# LoNet_808.net
KiCad netlist of a schematic drawn in EAGLE
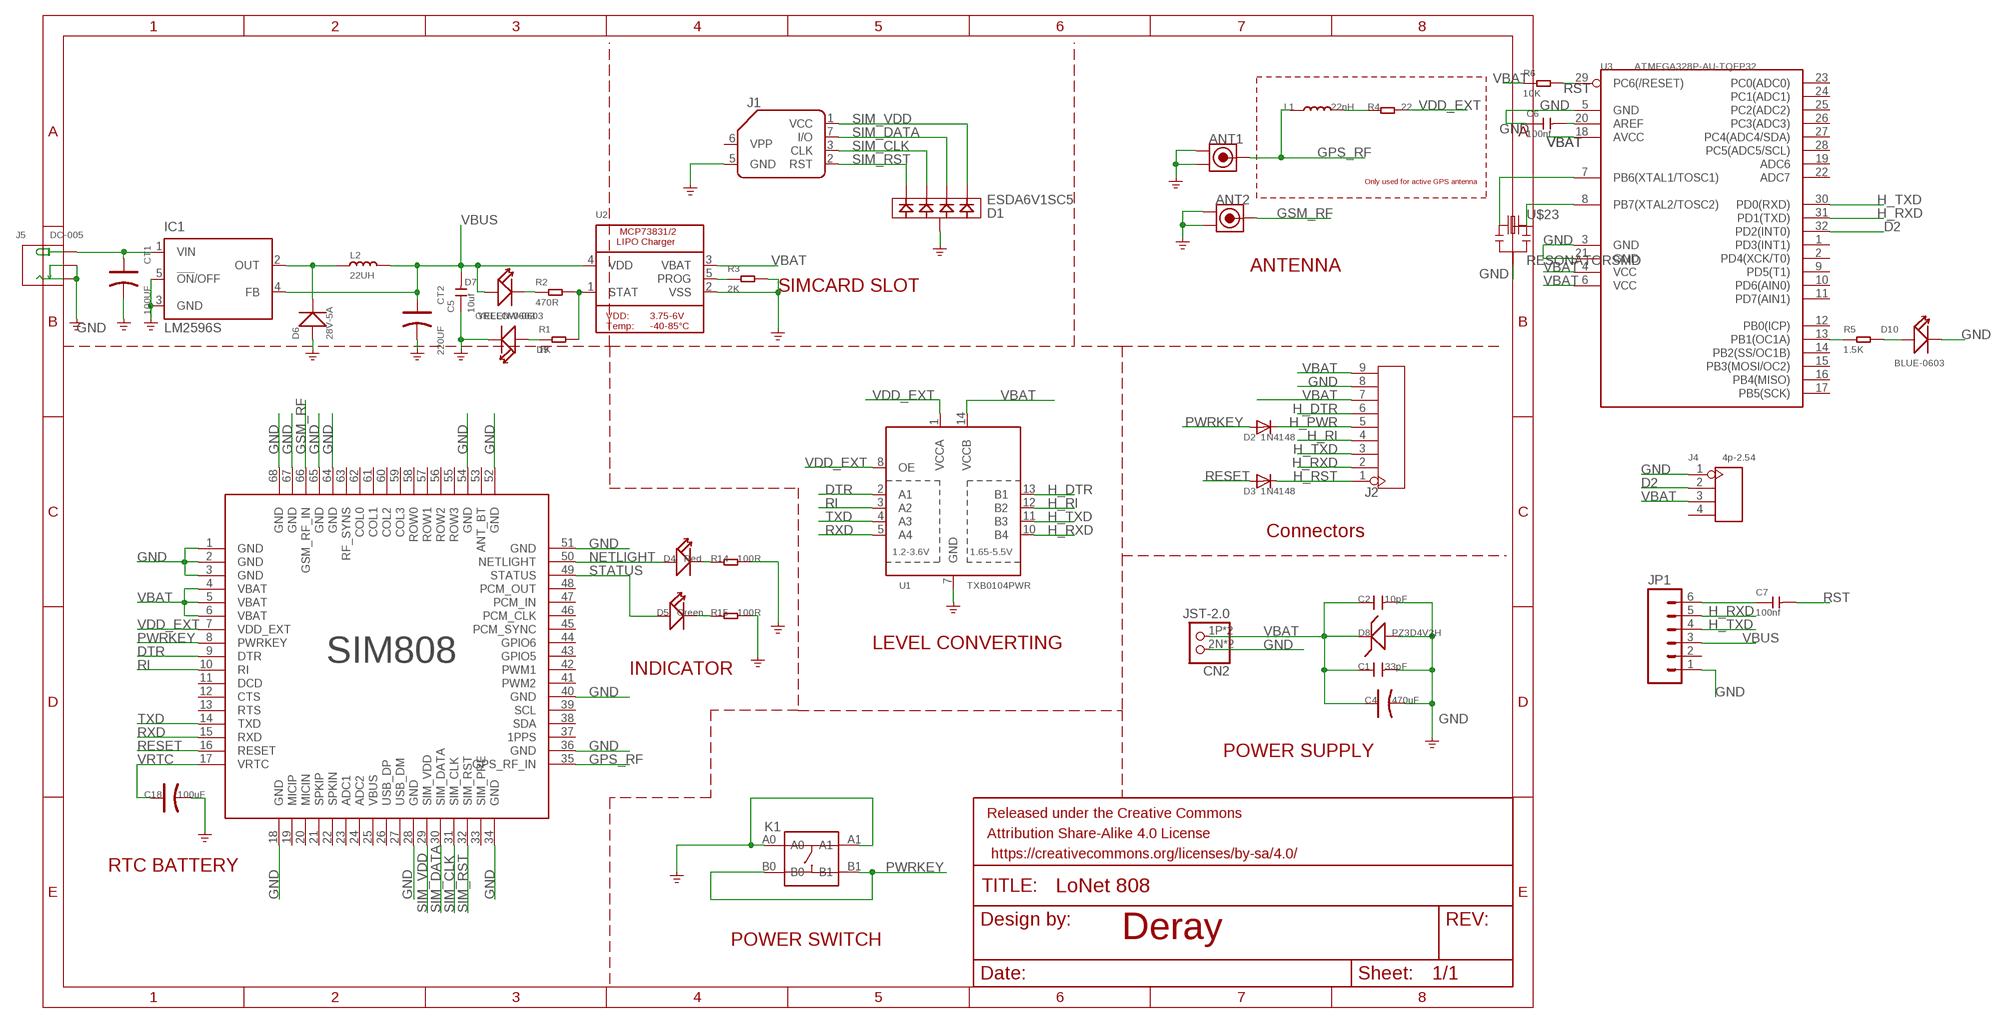
[diagram p0: schematic, sheet 1]

(export (version "E")
  (design (tool "Eeschema 10.0.6"))
  (components
    (comp (ref "ANT1")
      (value "ANTENNA-U-FL'3PAD-TYPE'")
      (footprint "eagle-import:3P-U-FL")
      (libsource (lib "eagle-import") (part "ANTENNA-U-FL'3PAD-TYPE'"))
    )
    (comp (ref "ANT2")
      (value "ANTENNA-U-FL'3PAD-TYPE'")
      (footprint "eagle-import:3P-U-FL")
      (libsource (lib "eagle-import") (part "ANTENNA-U-FL'3PAD-TYPE'"))
    )
    (comp (ref "C1")
      (value "33pF")
      (footprint "eagle-import:0603")
      (libsource (lib "eagle-import") (part "C-0603"))
    )
    (comp (ref "C2")
      (value "10pF")
      (footprint "eagle-import:0603")
      (libsource (lib "eagle-import") (part "C-0603"))
    )
    (comp (ref "C4")
      (value "470uF")
      (footprint "eagle-import:AVX-D")
      (libsource (lib "eagle-import") (part "CAP-AVX-D"))
    )
    (comp (ref "C5")
      (value "10uf")
      (footprint "eagle-import:C0603")
      (fields (field (name "MPN") "CC0603KRX5R6BB106"))
      (libsource (lib "eagle-import") (part "CERAMIC-10UF-10V-10%-X5R(0603)"))
    )
    (comp (ref "C6")
      (value "100nf")
      (footprint "eagle-import:C0603")
      (fields (field (name "MPN") "CC0603KRX7R9BB104"))
      (libsource (lib "eagle-import") (part "CERAMIC-100NF-50V-10%-X7R(0603)"))
    )
    (comp (ref "C7")
      (value "100nf")
      (footprint "eagle-import:C0603")
      (fields (field (name "MPN") "CC0603KRX7R9BB104"))
      (libsource (lib "eagle-import") (part "CERAMIC-100NF-50V-10%-X7R(0603)"))
    )
    (comp (ref "C18")
      (value "100uF")
      (footprint "eagle-import:AVX-A")
      (libsource (lib "eagle-import") (part "Discrete_CAP-AVX-A"))
    )
    (comp (ref "CN2")
      (value "JST-2.0")
      (footprint "eagle-import:JST-PH-2-SMT-RA2")
      (libsource (lib "eagle-import") (part "JST_2PIN"))
    )
    (comp (ref "CT1")
      (value "100UF")
      (footprint "eagle-import:ELECTRO-SMD-C-6MM")
      (fields (field (name "MPN") "CS1H101M-CRE77"))
      (libsource (lib "eagle-import") (part "ALUMINUM-SMD-100UF-50V-20%(D6MM)"))
    )
    (comp (ref "CT2")
      (value "220UF")
      (footprint "eagle-import:ELECTRO-SMD-C-6MM")
      (fields (field (name "MPN") "CS1E221M-CRE77"))
      (libsource (lib "eagle-import") (part "ALUMINUM-SMD-220UF-16V(D6.3-H7.7MM)"))
    )
    (comp (ref "D1")
      (value "ESDA6V1SC5")
      (footprint "eagle-import:SOT23-5L")
      (libsource (lib "eagle-import") (part "ESDA6V1SC5"))
    )
    (comp (ref "D2")
      (value "1N4148")
      (footprint "eagle-import:SOD-323F")
      (libsource (lib "eagle-import") (part "DIODESOD-323F"))
    )
    (comp (ref "D3")
      (value "1N4148")
      (footprint "eagle-import:SOD-323F")
      (libsource (lib "eagle-import") (part "DIODESOD-323F"))
    )
    (comp (ref "D4")
      (value "Red")
      (footprint "eagle-import:0603")
      (libsource (lib "eagle-import") (part "LED-0603"))
    )
    (comp (ref "D5")
      (value "Green")
      (footprint "eagle-import:0603")
      (libsource (lib "eagle-import") (part "LED-0603"))
    )
    (comp (ref "D6")
      (value "28V-5A")
      (footprint "eagle-import:DO-214AA")
      (fields (field (name "MPN") "SS54B"))
      (libsource (lib "eagle-import") (part "SMD-DIODE-SCHOTTKY-28V-5A(DO-214AA)"))
    )
    (comp (ref "D7")
      (value "YELLOW-0603")
      (footprint "eagle-import:LED-0603")
      (fields (field (name "MPN") "19-217-Y5C-AM1N1VY-3T"))
      (libsource (lib "eagle-import") (part "SMD-LED-CLEAR-YELLOW(0603)"))
    )
    (comp (ref "D8")
      (value "PZ3D4V2H")
      (footprint "eagle-import:SOD-323F")
      (libsource (lib "eagle-import") (part "ZENER-DIODE"))
    )
    (comp (ref "D9")
      (value "GREEN-0603")
      (footprint "eagle-import:LED-0603")
      (fields (field (name "MPN") "19-217-G7C-AN1P2-3T"))
      (libsource (lib "eagle-import") (part "SMD-LED-CLEAR-GREEN(0603)"))
    )
    (comp (ref "D10")
      (value "BLUE-0603")
      (footprint "eagle-import:LED-0603")
      (fields (field (name "MPN") "19-217-BHC-ZL1M2RY-3T"))
      (libsource (lib "eagle-import") (part "SMD-LED-CLEAR-BLUE(0603)"))
    )
    (comp (ref "IC1")
      (value "LM2596S")
      (footprint "eagle-import:TO263-5")
      (fields (field (name "MF") "NATIONAL SEMICONDUCTOR") (field (name "MPN") "LM2596S-ADJ/NOPB"))
      (libsource (lib "eagle-import") (part "LM2596S"))
    )
    (comp (ref "J1")
      (value "SIMHOLDERSIM")
      (footprint "eagle-import:SIMHOLDER")
      (libsource (lib "eagle-import") (part "SIMHOLDERSIM"))
    )
    (comp (ref "J2")
      (value "HEADER-9P-2.54")
      (footprint "eagle-import:9P-2.54")
      (libsource (lib "eagle-import") (part "HEADER-9P-2.54"))
    )
    (comp (ref "J4")
      (value "4p-2.54")
      (footprint "eagle-import:H4-2.54")
      (fields (field (name "MPN") "F185-1104A1BSYA1"))
      (libsource (lib "eagle-import") (part "DIP-BLACK-FEMALE-HEADER-VERT(4P-2.54)"))
    )
    (comp (ref "J5")
      (value "DC-005")
      (footprint "eagle-import:DCJ3P-14.2X11.0X9.0MM")
      (libsource (lib "eagle-import") (part "CONN-POWER-JACK-2.1MM(DC-005)"))
    )
    (comp (ref "JP1")
      (value "M06SIP")
      (footprint "eagle-import:1X06")
      (libsource (lib "eagle-import") (part "M06SIP"))
    )
    (comp (ref "K1")
      (value "BUTTON-4P-3.3X3.3")
      (footprint "eagle-import:4P-SMD-3.4X3.4X1.3H")
      (libsource (lib "eagle-import") (part "BUTTON-4P-3.3X3.3"))
    )
    (comp (ref "L1")
      (value "22nH")
      (footprint "eagle-import:L0402")
      (libsource (lib "eagle-import") (part "L'0402'"))
    )
    (comp (ref "L2")
      (value "22UH")
      (footprint "eagle-import:SMD-2P-2.0X1.2X1.0MM")
      (fields (field (name "MPN") "MPH201210S22RMT"))
      (libsource (lib "eagle-import") (part "SMD-INDUCTOR-22UH-20%(2P-2.0X1.2MM)"))
    )
    (comp (ref "R1")
      (value "1K")
      (footprint "eagle-import:R0603")
      (fields (field (name "MPN") "RC0603FR-071KL"))
      (libsource (lib "eagle-import") (part "SMD-RES-1K-1%-1/10W(0603)"))
    )
    (comp (ref "R2")
      (value "470R")
      (footprint "eagle-import:R0603")
      (fields (field (name "MPN") "RC0603JR-07470RL"))
      (libsource (lib "eagle-import") (part "SMD-RES-470R-5%-1/10W(0603)"))
    )
    (comp (ref "R3")
      (value "2K")
      (footprint "eagle-import:R0603")
      (fields (field (name "MPN") "RC0603FR-072KL"))
      (libsource (lib "eagle-import") (part "SMD-RES-2K-1%-1/10W(0603)"))
    )
    (comp (ref "R4")
      (value "22")
      (footprint "eagle-import:R0402")
      (libsource (lib "eagle-import") (part "Discrete_R-0402"))
    )
    (comp (ref "R5")
      (value "1.5K")
      (footprint "eagle-import:R0603")
      (fields (field (name "MPN") "RC0603FR-071K5L"))
      (libsource (lib "eagle-import") (part "SMD-RES-1.5K-1%-1/10W(0603)"))
    )
    (comp (ref "R6")
      (value "10K")
      (footprint "eagle-import:R0603")
      (fields (field (name "MPN") "RC0603FR-0710KL"))
      (libsource (lib "eagle-import") (part "SMD-RES-10K-1%-1/10W(0603)"))
    )
    (comp (ref "R14")
      (value "100R")
      (footprint "eagle-import:0603")
      (libsource (lib "eagle-import") (part "R-0603"))
    )
    (comp (ref "R15")
      (value "100R")
      (footprint "eagle-import:0603")
      (libsource (lib "eagle-import") (part "R-0603"))
    )
    (comp (ref "U$1")
      (value "SIM80868P-SMD-24X24")
      (footprint "eagle-import:68P-SMD-24X24")
      (libsource (lib "eagle-import") (part "SIM80868P-SMD-24X24"))
    )
    (comp (ref "U$23")
      (value "RESONATORSMD")
      (footprint "eagle-import:RESONATOR-SMD")
      (libsource (lib "eagle-import") (part "RESONATORSMD"))
    )
    (comp (ref "U1")
      (value "TXB0104PWR")
      (footprint "eagle-import:TSSOP14")
      (libsource (lib "eagle-import") (part "TXB0104PWR"))
    )
    (comp (ref "U2")
      (value "MCP73831/2")
      (footprint "eagle-import:SOT23-5")
      (libsource (lib "eagle-import") (part "MCP73831/2"))
    )
    (comp (ref "U3")
      (value "ATMEGA328P-AU-TQFP32")
      (footprint "eagle-import:TQFP32-0.8-7X7MM")
      (fields (field (name "MPN") "ATMEGA328P-AU"))
      (libsource (lib "eagle-import") (part "MCU-ATMEGA328P-AU(TQFP32)"))
    )
  )
  (nets
    (net (code "1") (name "/D2") (class "Default")
      (node (ref "J4") (pin "2") (pinfunction "P$2_2") (pintype "bidirectional"))
      (node (ref "U3") (pin "32") (pinfunction "PD2(INT0)_32") (pintype "bidirectional"))
    )
    (net (code "2") (name "/DTR") (class "Default")
      (node (ref "U$1") (pin "9") (pinfunction "DTR_9") (pintype "bidirectional"))
      (node (ref "U1") (pin "2") (pinfunction "A1_2") (pintype "bidirectional"))
    )
    (net (code "3") (name "/GPS_RF") (class "Default")
      (node (ref "ANT1") (pin "D") (pinfunction "D_D") (pintype "bidirectional"))
      (node (ref "L1") (pin "1") (pinfunction "1_1") (pintype "passive"))
      (node (ref "U$1") (pin "35") (pinfunction "GPS_RF_IN_35") (pintype "bidirectional"))
    )
    (net (code "4") (name "/GSM_RF") (class "Default")
      (node (ref "ANT2") (pin "D") (pinfunction "D_D") (pintype "bidirectional"))
      (node (ref "U$1") (pin "66") (pinfunction "GSM_RF_IN_66") (pintype "bidirectional"))
    )
    (net (code "5") (name "/H_DTR") (class "Default")
      (node (ref "J2") (pin "6") (pinfunction "6_6") (pintype "bidirectional"))
      (node (ref "U1") (pin "13") (pinfunction "B1_13") (pintype "bidirectional"))
    )
    (net (code "6") (name "/H_PWR") (class "Default")
      (node (ref "D2") (pin "C") (pinfunction "C_C") (pintype "passive"))
      (node (ref "J2") (pin "5") (pinfunction "5_5") (pintype "bidirectional"))
    )
    (net (code "7") (name "/H_RI") (class "Default")
      (node (ref "J2") (pin "4") (pinfunction "4_4") (pintype "bidirectional"))
      (node (ref "U1") (pin "12") (pinfunction "B2_12") (pintype "bidirectional"))
    )
    (net (code "8") (name "/H_RST") (class "Default")
      (node (ref "D3") (pin "C") (pinfunction "C_C") (pintype "passive"))
      (node (ref "J2") (pin "1") (pinfunction "1_1") (pintype "bidirectional"))
    )
    (net (code "9") (name "/H_RXD") (class "Default")
      (node (ref "J2") (pin "2") (pinfunction "2_2") (pintype "bidirectional"))
      (node (ref "JP1") (pin "5") (pinfunction "5_5") (pintype "passive"))
      (node (ref "U1") (pin "10") (pinfunction "B4_10") (pintype "bidirectional"))
      (node (ref "U3") (pin "31") (pinfunction "PD1(TXD)_31") (pintype "bidirectional"))
    )
    (net (code "10") (name "/H_TXD") (class "Default")
      (node (ref "J2") (pin "3") (pinfunction "3_3") (pintype "bidirectional"))
      (node (ref "JP1") (pin "4") (pinfunction "4_4") (pintype "passive"))
      (node (ref "U1") (pin "11") (pinfunction "B3_11") (pintype "bidirectional"))
      (node (ref "U3") (pin "30") (pinfunction "PD0(RXD)_30") (pintype "bidirectional"))
    )
    (net (code "11") (name "/NETLIGHT") (class "Default")
      (node (ref "D4") (pin "+") (pinfunction "+_+") (pintype "passive"))
      (node (ref "U$1") (pin "50") (pinfunction "NETLIGHT_50") (pintype "bidirectional"))
    )
    (net (code "12") (name "/PWRKEY") (class "Default")
      (node (ref "D2") (pin "A") (pinfunction "A_A") (pintype "passive"))
      (node (ref "K1") (pin "B0") (pinfunction "B0_B0") (pintype "bidirectional"))
      (node (ref "K1") (pin "B1") (pinfunction "B1_B1") (pintype "bidirectional"))
      (node (ref "U$1") (pin "8") (pinfunction "PWRKEY_8") (pintype "bidirectional"))
    )
    (net (code "13") (name "/RESET") (class "Default")
      (node (ref "D3") (pin "A") (pinfunction "A_A") (pintype "passive"))
      (node (ref "U$1") (pin "16") (pinfunction "RESET_16") (pintype "bidirectional"))
    )
    (net (code "14") (name "/RI") (class "Default")
      (node (ref "U$1") (pin "10") (pinfunction "RI_10") (pintype "bidirectional"))
      (node (ref "U1") (pin "3") (pinfunction "A2_3") (pintype "bidirectional"))
    )
    (net (code "15") (name "/RST") (class "Default")
      (node (ref "C7") (pin "2") (pinfunction "2_2") (pintype "passive"))
      (node (ref "R6") (pin "2") (pinfunction "2_2") (pintype "passive"))
      (node (ref "U3") (pin "29") (pinfunction "PC6(/RESET)_29") (pintype "bidirectional"))
    )
    (net (code "16") (name "/RXD") (class "Default")
      (node (ref "U$1") (pin "15") (pinfunction "RXD_15") (pintype "bidirectional"))
      (node (ref "U1") (pin "5") (pinfunction "A4_5") (pintype "bidirectional"))
    )
    (net (code "17") (name "/SIM_CLK") (class "Default")
      (node (ref "D1") (pin "3") (pinfunction "3_3") (pintype "bidirectional"))
      (node (ref "J1") (pin "3") (pinfunction "CLK_3") (pintype "input"))
      (node (ref "U$1") (pin "31") (pinfunction "SIM_CLK_31") (pintype "bidirectional"))
    )
    (net (code "18") (name "/SIM_DATA") (class "Default")
      (node (ref "D1") (pin "5") (pinfunction "5_5") (pintype "bidirectional"))
      (node (ref "J1") (pin "7") (pinfunction "I/O_7") (pintype "bidirectional"))
      (node (ref "U$1") (pin "30") (pinfunction "SIM_DATA_30") (pintype "bidirectional"))
    )
    (net (code "19") (name "/SIM_RST") (class "Default")
      (node (ref "D1") (pin "1") (pinfunction "1_1") (pintype "bidirectional"))
      (node (ref "J1") (pin "2") (pinfunction "RST_2") (pintype "input"))
      (node (ref "U$1") (pin "32") (pinfunction "SIM_RST_32") (pintype "bidirectional"))
    )
    (net (code "20") (name "/SIM_VDD") (class "Default")
      (node (ref "D1") (pin "4") (pinfunction "4_4") (pintype "bidirectional"))
      (node (ref "J1") (pin "1") (pinfunction "VCC_1") (pintype "power_in"))
      (node (ref "U$1") (pin "29") (pinfunction "SIM_VDD_29") (pintype "bidirectional"))
    )
    (net (code "21") (name "/STATUS") (class "Default")
      (node (ref "D5") (pin "+") (pinfunction "+_+") (pintype "passive"))
      (node (ref "U$1") (pin "49") (pinfunction "STATUS_49") (pintype "bidirectional"))
    )
    (net (code "22") (name "/TXD") (class "Default")
      (node (ref "U$1") (pin "14") (pinfunction "TXD_14") (pintype "bidirectional"))
      (node (ref "U1") (pin "4") (pinfunction "A3_4") (pintype "bidirectional"))
    )
    (net (code "23") (name "/VBAT") (class "Default")
      (node (ref "C1") (pin "1") (pinfunction "1_1") (pintype "passive"))
      (node (ref "C2") (pin "1") (pinfunction "1_1") (pintype "passive"))
      (node (ref "C4") (pin "+") (pinfunction "+_+") (pintype "passive"))
      (node (ref "CN2") (pin "1P") (pinfunction "2_1P") (pintype "passive"))
      (node (ref "CN2") (pin "3P") (pinfunction "2_3P") (pintype "passive"))
      (node (ref "D8") (pin "C") (pinfunction "P$1_C") (pintype "bidirectional"))
      (node (ref "J2") (pin "7") (pinfunction "7_7") (pintype "bidirectional"))
      (node (ref "J2") (pin "9") (pinfunction "9_9") (pintype "bidirectional"))
      (node (ref "J4") (pin "3") (pinfunction "P$3_3") (pintype "bidirectional"))
      (node (ref "R6") (pin "1") (pinfunction "1_1") (pintype "passive"))
      (node (ref "U$1") (pin "4") (pinfunction "VBAT_4") (pintype "bidirectional"))
      (node (ref "U$1") (pin "5") (pinfunction "VBAT_5") (pintype "bidirectional"))
      (node (ref "U$1") (pin "6") (pinfunction "VBAT_6") (pintype "bidirectional"))
      (node (ref "U1") (pin "14") (pinfunction "VCCB_14") (pintype "bidirectional"))
      (node (ref "U2") (pin "3") (pinfunction "VBAT_3") (pintype "power_in"))
      (node (ref "U3") (pin "18") (pinfunction "AVCC_18") (pintype "bidirectional"))
      (node (ref "U3") (pin "4") (pinfunction "VCC_4") (pintype "bidirectional"))
      (node (ref "U3") (pin "6") (pinfunction "VCC_6") (pintype "bidirectional"))
    )
    (net (code "24") (name "/VBUS") (class "Default")
      (node (ref "C5") (pin "2") (pinfunction "2_2") (pintype "passive"))
      (node (ref "CT2") (pin "+") (pinfunction "+_+") (pintype "passive"))
      (node (ref "D7") (pin "+") (pinfunction "+_+") (pintype "passive"))
      (node (ref "IC1") (pin "4") (pinfunction "FB_4") (pintype "input"))
      (node (ref "JP1") (pin "3") (pinfunction "3_3") (pintype "passive"))
      (node (ref "L2") (pin "2") (pinfunction "2_2") (pintype "passive"))
      (node (ref "U2") (pin "4") (pinfunction "VDD_4") (pintype "power_in"))
    )
    (net (code "25") (name "/VDD_EXT") (class "Default")
      (node (ref "R4") (pin "2") (pinfunction "2_2") (pintype "passive"))
      (node (ref "U$1") (pin "7") (pinfunction "VDD_EXT_7") (pintype "bidirectional"))
      (node (ref "U1") (pin "1") (pinfunction "VCCA_1") (pintype "bidirectional"))
      (node (ref "U1") (pin "8") (pinfunction "OE_8") (pintype "bidirectional"))
    )
    (net (code "26") (name "/VRTC") (class "Default")
      (node (ref "C18") (pin "+") (pinfunction "+_+") (pintype "passive"))
      (node (ref "U$1") (pin "17") (pinfunction "VRTC_17") (pintype "bidirectional"))
    )
    (net (code "27") (name "GND_POWER") (class "Default")
      (node (ref "ANT1") (pin "GND1") (pinfunction "GND1_GND1") (pintype "bidirectional"))
      (node (ref "ANT1") (pin "GND2") (pinfunction "GND2_GND2") (pintype "bidirectional"))
      (node (ref "ANT2") (pin "GND1") (pinfunction "GND1_GND1") (pintype "bidirectional"))
      (node (ref "ANT2") (pin "GND2") (pinfunction "GND2_GND2") (pintype "bidirectional"))
      (node (ref "C1") (pin "2") (pinfunction "2_2") (pintype "passive"))
      (node (ref "C18") (pin "-") (pinfunction "-_-") (pintype "passive"))
      (node (ref "C2") (pin "2") (pinfunction "2_2") (pintype "passive"))
      (node (ref "C4") (pin "-") (pinfunction "-_-") (pintype "passive"))
      (node (ref "C5") (pin "1") (pinfunction "1_1") (pintype "passive"))
      (node (ref "C6") (pin "1") (pinfunction "1_1") (pintype "passive"))
      (node (ref "CN2") (pin "2N") (pinfunction "1_2N") (pintype "passive"))
      (node (ref "CN2") (pin "4N") (pinfunction "1_4N") (pintype "passive"))
      (node (ref "CT1") (pin "-") (pinfunction "-_-") (pintype "passive"))
      (node (ref "CT2") (pin "-") (pinfunction "-_-") (pintype "passive"))
      (node (ref "D1") (pin "2") (pinfunction "2_2") (pintype "bidirectional"))
      (node (ref "D10") (pin "-") (pinfunction "-_-") (pintype "passive"))
      (node (ref "D6") (pin "+") (pinfunction "+_+") (pintype "passive"))
      (node (ref "D8") (pin "A") (pinfunction "P$2_A") (pintype "bidirectional"))
      (node (ref "D9") (pin "-") (pinfunction "-_-") (pintype "passive"))
      (node (ref "IC1") (pin "3") (pinfunction "GND_3") (pintype "power_in"))
      (node (ref "IC1") (pin "5") (pinfunction "~{ON}/OFF_5") (pintype "input"))
      (node (ref "J1") (pin "5") (pinfunction "GND_5") (pintype "power_in"))
      (node (ref "J2") (pin "8") (pinfunction "8_8") (pintype "bidirectional"))
      (node (ref "J4") (pin "1") (pinfunction "P$1_1") (pintype "bidirectional"))
      (node (ref "J5") (pin "-1") (pinfunction "-_-1") (pintype "bidirectional"))
      (node (ref "J5") (pin "-2") (pinfunction "CDN_-2") (pintype "bidirectional"))
      (node (ref "JP1") (pin "1") (pinfunction "1_1") (pintype "passive"))
      (node (ref "K1") (pin "A0") (pinfunction "A0_A0") (pintype "bidirectional"))
      (node (ref "K1") (pin "A1") (pinfunction "A1_A1") (pintype "bidirectional"))
      (node (ref "R14") (pin "2") (pinfunction "2_2") (pintype "passive"))
      (node (ref "R15") (pin "2") (pinfunction "2_2") (pintype "passive"))
      (node (ref "R3") (pin "2") (pinfunction "2_2") (pintype "passive"))
      (node (ref "U$1") (pin "1") (pinfunction "GND_1") (pintype "bidirectional"))
      (node (ref "U$1") (pin "18") (pinfunction "GND_18") (pintype "bidirectional"))
      (node (ref "U$1") (pin "2") (pinfunction "GND_2") (pintype "bidirectional"))
      (node (ref "U$1") (pin "28") (pinfunction "GND_28") (pintype "bidirectional"))
      (node (ref "U$1") (pin "3") (pinfunction "GND_3") (pintype "bidirectional"))
      (node (ref "U$1") (pin "34") (pinfunction "GND_34") (pintype "bidirectional"))
      (node (ref "U$1") (pin "36") (pinfunction "GND_36") (pintype "bidirectional"))
      (node (ref "U$1") (pin "40") (pinfunction "GND_40") (pintype "bidirectional"))
      (node (ref "U$1") (pin "51") (pinfunction "GND_51") (pintype "bidirectional"))
      (node (ref "U$1") (pin "52") (pinfunction "GND_52") (pintype "bidirectional"))
      (node (ref "U$1") (pin "54") (pinfunction "GND_54") (pintype "bidirectional"))
      (node (ref "U$1") (pin "64") (pinfunction "GND_64") (pintype "bidirectional"))
      (node (ref "U$1") (pin "65") (pinfunction "GND_65") (pintype "bidirectional"))
      (node (ref "U$1") (pin "67") (pinfunction "GND_67") (pintype "bidirectional"))
      (node (ref "U$1") (pin "68") (pinfunction "GND_68") (pintype "bidirectional"))
      (node (ref "U$23") (pin "2") (pinfunction "2_2") (pintype "passive"))
      (node (ref "U1") (pin "7") (pinfunction "GND_7") (pintype "bidirectional"))
      (node (ref "U2") (pin "2") (pinfunction "VSS_2") (pintype "power_in"))
      (node (ref "U3") (pin "21") (pinfunction "GND_21") (pintype "bidirectional"))
      (node (ref "U3") (pin "3") (pinfunction "GND_3") (pintype "bidirectional"))
      (node (ref "U3") (pin "5") (pinfunction "GND_5") (pintype "bidirectional"))
    )
    (net (code "28") (name "Net-(C7-Pad1)") (class "Default")
      (node (ref "C7") (pin "1") (pinfunction "1_1") (pintype "passive"))
      (node (ref "JP1") (pin "6") (pinfunction "6_6") (pintype "passive"))
    )
    (net (code "29") (name "Net-(D4-Pad-)") (class "Default")
      (node (ref "D4") (pin "-") (pinfunction "-_-") (pintype "passive"))
      (node (ref "R14") (pin "1") (pinfunction "1_1") (pintype "passive"))
    )
    (net (code "30") (name "Net-(D5-Pad-)") (class "Default")
      (node (ref "D5") (pin "-") (pinfunction "-_-") (pintype "passive"))
      (node (ref "R15") (pin "1") (pinfunction "1_1") (pintype "passive"))
    )
    (net (code "31") (name "Net-(D7-Pad-)") (class "Default")
      (node (ref "D7") (pin "-") (pinfunction "-_-") (pintype "passive"))
      (node (ref "R2") (pin "1") (pinfunction "1_1") (pintype "passive"))
    )
    (net (code "32") (name "Net-(D9-Pad+)") (class "Default")
      (node (ref "D9") (pin "+") (pinfunction "+_+") (pintype "passive"))
      (node (ref "R1") (pin "1") (pinfunction "1_1") (pintype "passive"))
    )
    (net (code "33") (name "Net-(D10-Pad+)") (class "Default")
      (node (ref "D10") (pin "+") (pinfunction "+_+") (pintype "passive"))
      (node (ref "R5") (pin "2") (pinfunction "2_2") (pintype "passive"))
    )
    (net (code "34") (name "Net-(IC1-OUT)") (class "Default")
      (node (ref "D6") (pin "-") (pinfunction "-_-") (pintype "passive"))
      (node (ref "IC1") (pin "2") (pinfunction "OUT_2") (pintype "output"))
      (node (ref "L2") (pin "1") (pinfunction "1_1") (pintype "passive"))
    )
    (net (code "35") (name "Net-(IC1-VIN)") (class "Default")
      (node (ref "CT1") (pin "+") (pinfunction "+_+") (pintype "passive"))
      (node (ref "IC1") (pin "1") (pinfunction "VIN_1") (pintype "input"))
      (node (ref "J5") (pin "+") (pinfunction "+_+") (pintype "bidirectional"))
    )
    (net (code "36") (name "Net-(L1-Pad2)") (class "Default")
      (node (ref "L1") (pin "2") (pinfunction "2_2") (pintype "passive"))
      (node (ref "R4") (pin "1") (pinfunction "1_1") (pintype "passive"))
    )
    (net (code "37") (name "Net-(U2-PROG)") (class "Default")
      (node (ref "R3") (pin "1") (pinfunction "1_1") (pintype "passive"))
      (node (ref "U2") (pin "5") (pinfunction "PROG_5") (pintype "input"))
    )
    (net (code "38") (name "Net-(U2-STAT)") (class "Default")
      (node (ref "R1") (pin "2") (pinfunction "2_2") (pintype "passive"))
      (node (ref "R2") (pin "2") (pinfunction "2_2") (pintype "passive"))
      (node (ref "U2") (pin "1") (pinfunction "STAT_1") (pintype "output"))
    )
    (net (code "39") (name "Net-(U3-AREF)") (class "Default")
      (node (ref "C6") (pin "2") (pinfunction "2_2") (pintype "passive"))
      (node (ref "U3") (pin "20") (pinfunction "AREF_20") (pintype "bidirectional"))
    )
    (net (code "40") (name "Net-(U3-PB1(OC1A))") (class "Default")
      (node (ref "R5") (pin "1") (pinfunction "1_1") (pintype "passive"))
      (node (ref "U3") (pin "13") (pinfunction "PB1(OC1A)_13") (pintype "bidirectional"))
    )
    (net (code "41") (name "Net-(U3-PB6(XTAL1{slash}TOSC1))") (class "Default")
      (node (ref "U$23") (pin "1") (pinfunction "1_1") (pintype "passive"))
      (node (ref "U3") (pin "7") (pinfunction "PB6(XTAL1/TOSC1)_7") (pintype "bidirectional"))
    )
    (net (code "42") (name "Net-(U3-PB7(XTAL2{slash}TOSC2))") (class "Default")
      (node (ref "U$23") (pin "3") (pinfunction "3_3") (pintype "passive"))
      (node (ref "U3") (pin "8") (pinfunction "PB7(XTAL2/TOSC2)_8") (pintype "bidirectional"))
    )
    (net (code "43") (name "unconnected-(J1-VPP-Pad6)") (class "Default")
      (node (ref "J1") (pin "6") (pinfunction "VPP_6") (pintype "bidirectional"))
    )
    (net (code "44") (name "unconnected-(J4-P$4-Pad4)") (class "Default")
      (node (ref "J4") (pin "4") (pinfunction "P$4_4") (pintype "bidirectional"))
    )
    (net (code "45") (name "unconnected-(JP1-Pad2)") (class "Default")
      (node (ref "JP1") (pin "2") (pinfunction "2_2") (pintype "passive"))
    )
    (net (code "46") (name "unconnected-(U$1-1PPS-Pad37)") (class "Default")
      (node (ref "U$1") (pin "37") (pinfunction "1PPS_37") (pintype "bidirectional"))
    )
    (net (code "47") (name "unconnected-(U$1-ADC1-Pad23)") (class "Default")
      (node (ref "U$1") (pin "23") (pinfunction "ADC1_23") (pintype "bidirectional"))
    )
    (net (code "48") (name "unconnected-(U$1-ADC2-Pad24)") (class "Default")
      (node (ref "U$1") (pin "24") (pinfunction "ADC2_24") (pintype "bidirectional"))
    )
    (net (code "49") (name "unconnected-(U$1-ANT_BT-Pad53)") (class "Default")
      (node (ref "U$1") (pin "53") (pinfunction "ANT_BT_53") (pintype "bidirectional"))
    )
    (net (code "50") (name "unconnected-(U$1-COL0-Pad62)") (class "Default")
      (node (ref "U$1") (pin "62") (pinfunction "COL0_62") (pintype "bidirectional"))
    )
    (net (code "51") (name "unconnected-(U$1-COL1-Pad61)") (class "Default")
      (node (ref "U$1") (pin "61") (pinfunction "COL1_61") (pintype "bidirectional"))
    )
    (net (code "52") (name "unconnected-(U$1-COL2-Pad60)") (class "Default")
      (node (ref "U$1") (pin "60") (pinfunction "COL2_60") (pintype "bidirectional"))
    )
    (net (code "53") (name "unconnected-(U$1-COL3-Pad59)") (class "Default")
      (node (ref "U$1") (pin "59") (pinfunction "COL3_59") (pintype "bidirectional"))
    )
    (net (code "54") (name "unconnected-(U$1-CTS-Pad12)") (class "Default")
      (node (ref "U$1") (pin "12") (pinfunction "CTS_12") (pintype "bidirectional"))
    )
    (net (code "55") (name "unconnected-(U$1-DCD-Pad11)") (class "Default")
      (node (ref "U$1") (pin "11") (pinfunction "DCD_11") (pintype "bidirectional"))
    )
    (net (code "56") (name "unconnected-(U$1-GPIO5-Pad43)") (class "Default")
      (node (ref "U$1") (pin "43") (pinfunction "GPIO5_43") (pintype "bidirectional"))
    )
    (net (code "57") (name "unconnected-(U$1-GPIO6-Pad44)") (class "Default")
      (node (ref "U$1") (pin "44") (pinfunction "GPIO6_44") (pintype "bidirectional"))
    )
    (net (code "58") (name "unconnected-(U$1-MICIN-Pad20)") (class "Default")
      (node (ref "U$1") (pin "20") (pinfunction "MICIN_20") (pintype "bidirectional"))
    )
    (net (code "59") (name "unconnected-(U$1-MICIP-Pad19)") (class "Default")
      (node (ref "U$1") (pin "19") (pinfunction "MICIP_19") (pintype "bidirectional"))
    )
    (net (code "60") (name "unconnected-(U$1-PCM_CLK-Pad46)") (class "Default")
      (node (ref "U$1") (pin "46") (pinfunction "PCM_CLK_46") (pintype "bidirectional"))
    )
    (net (code "61") (name "unconnected-(U$1-PCM_IN-Pad47)") (class "Default")
      (node (ref "U$1") (pin "47") (pinfunction "PCM_IN_47") (pintype "bidirectional"))
    )
    (net (code "62") (name "unconnected-(U$1-PCM_OUT-Pad48)") (class "Default")
      (node (ref "U$1") (pin "48") (pinfunction "PCM_OUT_48") (pintype "bidirectional"))
    )
    (net (code "63") (name "unconnected-(U$1-PCM_SYNC-Pad45)") (class "Default")
      (node (ref "U$1") (pin "45") (pinfunction "PCM_SYNC_45") (pintype "bidirectional"))
    )
    (net (code "64") (name "unconnected-(U$1-PWM1-Pad42)") (class "Default")
      (node (ref "U$1") (pin "42") (pinfunction "PWM1_42") (pintype "bidirectional"))
    )
    (net (code "65") (name "unconnected-(U$1-PWM2-Pad41)") (class "Default")
      (node (ref "U$1") (pin "41") (pinfunction "PWM2_41") (pintype "bidirectional"))
    )
    (net (code "66") (name "unconnected-(U$1-RF_SYNS-Pad63)") (class "Default")
      (node (ref "U$1") (pin "63") (pinfunction "RF_SYNS_63") (pintype "bidirectional"))
    )
    (net (code "67") (name "unconnected-(U$1-ROW0-Pad58)") (class "Default")
      (node (ref "U$1") (pin "58") (pinfunction "ROW0_58") (pintype "bidirectional"))
    )
    (net (code "68") (name "unconnected-(U$1-ROW1-Pad57)") (class "Default")
      (node (ref "U$1") (pin "57") (pinfunction "ROW1_57") (pintype "bidirectional"))
    )
    (net (code "69") (name "unconnected-(U$1-ROW2-Pad56)") (class "Default")
      (node (ref "U$1") (pin "56") (pinfunction "ROW2_56") (pintype "bidirectional"))
    )
    (net (code "70") (name "unconnected-(U$1-ROW3-Pad55)") (class "Default")
      (node (ref "U$1") (pin "55") (pinfunction "ROW3_55") (pintype "bidirectional"))
    )
    (net (code "71") (name "unconnected-(U$1-RTS-Pad13)") (class "Default")
      (node (ref "U$1") (pin "13") (pinfunction "RTS_13") (pintype "bidirectional"))
    )
    (net (code "72") (name "unconnected-(U$1-SCL-Pad39)") (class "Default")
      (node (ref "U$1") (pin "39") (pinfunction "SCL_39") (pintype "bidirectional"))
    )
    (net (code "73") (name "unconnected-(U$1-SDA-Pad38)") (class "Default")
      (node (ref "U$1") (pin "38") (pinfunction "SDA_38") (pintype "bidirectional"))
    )
    (net (code "74") (name "unconnected-(U$1-SIM_PRE-Pad33)") (class "Default")
      (node (ref "U$1") (pin "33") (pinfunction "SIM_PRE_33") (pintype "bidirectional"))
    )
    (net (code "75") (name "unconnected-(U$1-SPKIN-Pad22)") (class "Default")
      (node (ref "U$1") (pin "22") (pinfunction "SPKIN_22") (pintype "bidirectional"))
    )
    (net (code "76") (name "unconnected-(U$1-SPKIP-Pad21)") (class "Default")
      (node (ref "U$1") (pin "21") (pinfunction "SPKIP_21") (pintype "bidirectional"))
    )
    (net (code "77") (name "unconnected-(U$1-USB_DM-Pad27)") (class "Default")
      (node (ref "U$1") (pin "27") (pinfunction "USB_DM_27") (pintype "bidirectional"))
    )
    (net (code "78") (name "unconnected-(U$1-USB_DP-Pad26)") (class "Default")
      (node (ref "U$1") (pin "26") (pinfunction "USB_DP_26") (pintype "bidirectional"))
    )
    (net (code "79") (name "unconnected-(U$1-VBUS-Pad25)") (class "Default")
      (node (ref "U$1") (pin "25") (pinfunction "VBUS_25") (pintype "bidirectional"))
    )
    (net (code "80") (name "unconnected-(U3-ADC6-Pad19)") (class "Default")
      (node (ref "U3") (pin "19") (pinfunction "ADC6_19") (pintype "bidirectional"))
    )
    (net (code "81") (name "unconnected-(U3-ADC7-Pad22)") (class "Default")
      (node (ref "U3") (pin "22") (pinfunction "ADC7_22") (pintype "bidirectional"))
    )
    (net (code "82") (name "unconnected-(U3-PB0(ICP)-Pad12)") (class "Default")
      (node (ref "U3") (pin "12") (pinfunction "PB0(ICP)_12") (pintype "bidirectional"))
    )
    (net (code "83") (name "unconnected-(U3-PB2(SS{slash}OC1B)-Pad14)") (class "Default")
      (node (ref "U3") (pin "14") (pinfunction "PB2(SS/OC1B)_14") (pintype "bidirectional"))
    )
    (net (code "84") (name "unconnected-(U3-PB3(MOSI{slash}OC2)-Pad15)") (class "Default")
      (node (ref "U3") (pin "15") (pinfunction "PB3(MOSI/OC2)_15") (pintype "bidirectional"))
    )
    (net (code "85") (name "unconnected-(U3-PB4(MISO)-Pad16)") (class "Default")
      (node (ref "U3") (pin "16") (pinfunction "PB4(MISO)_16") (pintype "bidirectional"))
    )
    (net (code "86") (name "unconnected-(U3-PB5(SCK)-Pad17)") (class "Default")
      (node (ref "U3") (pin "17") (pinfunction "PB5(SCK)_17") (pintype "bidirectional"))
    )
    (net (code "87") (name "unconnected-(U3-PC0(ADC0)-Pad23)") (class "Default")
      (node (ref "U3") (pin "23") (pinfunction "PC0(ADC0)_23") (pintype "bidirectional"))
    )
    (net (code "88") (name "unconnected-(U3-PC1(ADC1)-Pad24)") (class "Default")
      (node (ref "U3") (pin "24") (pinfunction "PC1(ADC1)_24") (pintype "bidirectional"))
    )
    (net (code "89") (name "unconnected-(U3-PC2(ADC2)-Pad25)") (class "Default")
      (node (ref "U3") (pin "25") (pinfunction "PC2(ADC2)_25") (pintype "bidirectional"))
    )
    (net (code "90") (name "unconnected-(U3-PC3(ADC3)-Pad26)") (class "Default")
      (node (ref "U3") (pin "26") (pinfunction "PC3(ADC3)_26") (pintype "bidirectional"))
    )
    (net (code "91") (name "unconnected-(U3-PC4(ADC4{slash}SDA)-Pad27)") (class "Default")
      (node (ref "U3") (pin "27") (pinfunction "PC4(ADC4/SDA)_27") (pintype "bidirectional"))
    )
    (net (code "92") (name "unconnected-(U3-PC5(ADC5{slash}SCL)-Pad28)") (class "Default")
      (node (ref "U3") (pin "28") (pinfunction "PC5(ADC5/SCL)_28") (pintype "bidirectional"))
    )
    (net (code "93") (name "unconnected-(U3-PD3(INT1)-Pad1)") (class "Default")
      (node (ref "U3") (pin "1") (pinfunction "PD3(INT1)_1") (pintype "bidirectional"))
    )
    (net (code "94") (name "unconnected-(U3-PD4(XCK{slash}T0)-Pad2)") (class "Default")
      (node (ref "U3") (pin "2") (pinfunction "PD4(XCK/T0)_2") (pintype "bidirectional"))
    )
    (net (code "95") (name "unconnected-(U3-PD5(T1)-Pad9)") (class "Default")
      (node (ref "U3") (pin "9") (pinfunction "PD5(T1)_9") (pintype "bidirectional"))
    )
    (net (code "96") (name "unconnected-(U3-PD6(AIN0)-Pad10)") (class "Default")
      (node (ref "U3") (pin "10") (pinfunction "PD6(AIN0)_10") (pintype "bidirectional"))
    )
    (net (code "97") (name "unconnected-(U3-PD7(AIN1)-Pad11)") (class "Default")
      (node (ref "U3") (pin "11") (pinfunction "PD7(AIN1)_11") (pintype "bidirectional"))
    )
  )
)
